# top.net
KiCad netlist of a schematic drawn in Altium Designer
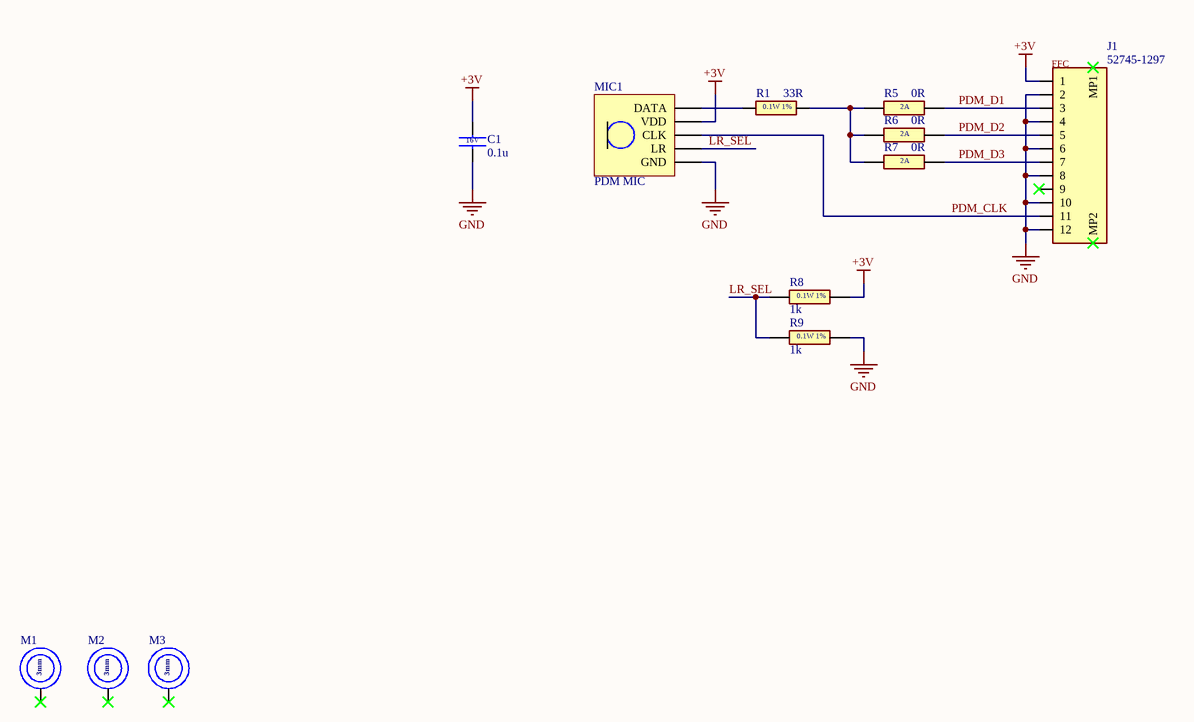
[diagram p0: top.SchDoc]

(export (version "E")
  (design (tool "Eeschema 10.0.6"))
  (components
    (comp (ref "C1")
      (value "0.1u")
      (footprint "CAPC1608X95N")
      (description "16V 0.1uF XR7 0603 10%")
      (fields
        (field (name "MANUFACTURER_PART_NUMBER") "C0603C104K4RAC-TU")
        (field (name "MOUSER PART NUMBER") "80-C0603C104K4RAC")
      )
      (libsource (lib "bch-lib") (part "ECK+100n16V"))
    )
    (comp (ref "J1")
      (value "52745-1297")
      (footprint "527451297")
      (fields (field (name "MOUSER PART NUMBER") "538-52745-1297"))
      (libsource (lib "bch-lib") (part "EJ+52745-1297"))
    )
    (comp (ref "M1")
      (value "MTH-3MM")
      (footprint "MountingHole_3.0mm_NPTH")
      (libsource (lib "bch-lib") (part "EMECH-MTH-3MM"))
    )
    (comp (ref "M2")
      (value "MTH-3MM")
      (footprint "MountingHole_3.0mm_NPTH")
      (libsource (lib "bch-lib") (part "EMECH-MTH-3MM"))
    )
    (comp (ref "M3")
      (value "MTH-3MM")
      (footprint "MountingHole_3.0mm_NPTH")
      (libsource (lib "bch-lib") (part "EMECH-MTH-3MM"))
    )
    (comp (ref "MIC1")
      (value "PDM MIC")
      (footprint "LLGA-5-4X3")
      (description "MEMS Microphones MIC DBP DIGITAL")
      (libsource (lib "bch-lib") (part "EX+IM67D130AXTSA2"))
    )
    (comp (ref "R1")
      (value "33R")
      (footprint "RESC1608X55N")
      (description "Resistor 1% 0.1W")
      (fields
        (field (name "MANUFACTURER_PART_NUMBER") "0603WAF330JT5E")
        (field (name "MOUSER PART NUMBER") "303-0603WAF330JT5E")
      )
      (libsource (lib "bch-lib") (part "ER+33R"))
    )
    (comp (ref "R5")
      (value "0R")
      (footprint "RESC1608X50N")
      (description "2A")
      (fields
        (field (name "MANUFACTURER_PART_NUMBER") "RCA06030000ZSEA")
        (field (name "MOUSER PART NUMBER") "71-RCA06030000ZSEA")
      )
      (libsource (lib "bch-lib") (part "ER+0R"))
    )
    (comp (ref "R6")
      (value "0R")
      (footprint "RESC1608X50N")
      (description "2A")
      (fields
        (field (name "MANUFACTURER_PART_NUMBER") "RCA06030000ZSEA")
        (field (name "MOUSER PART NUMBER") "71-RCA06030000ZSEA")
      )
      (libsource (lib "bch-lib") (part "ER+0R"))
    )
    (comp (ref "R7")
      (value "0R")
      (footprint "RESC1608X50N")
      (description "2A")
      (fields
        (field (name "MANUFACTURER_PART_NUMBER") "RCA06030000ZSEA")
        (field (name "MOUSER PART NUMBER") "71-RCA06030000ZSEA")
      )
      (libsource (lib "bch-lib") (part "ER+0R"))
    )
    (comp (ref "R8")
      (value "1k")
      (footprint "RESC1608X50N")
      (description "Resistor 1%, 0.1W")
      (fields
        (field (name "MANUFACTURER_PART_NUMBER") "CRCW06031K00FKEA")
        (field (name "MOUSER PART NUMBER") "71-CRCW0603-1.0K-E3")
      )
      (libsource (lib "bch-lib") (part "ER+1K"))
    )
    (comp (ref "R9")
      (value "1k")
      (footprint "RESC1608X50N")
      (description "Resistor 1%, 0.1W")
      (fields
        (field (name "MANUFACTURER_PART_NUMBER") "CRCW06031K00FKEA")
        (field (name "MOUSER PART NUMBER") "71-CRCW0603-1.0K-E3")
      )
      (libsource (lib "bch-lib") (part "ER+1K"))
    )
  )
  (nets
    (net (code "1") (name "+3V") (class "Default")
      (node (ref "C1") (pin "1") (pinfunction "1_1") (pintype "passive"))
      (node (ref "J1") (pin "1") (pinfunction "1_1") (pintype "passive"))
      (node (ref "MIC1") (pin "4") (pinfunction "VDD_4") (pintype "passive"))
      (node (ref "R8") (pin "2") (pinfunction "2_2") (pintype "passive"))
    )
    (net (code "2") (name "/LR_SEL") (class "Default")
      (node (ref "MIC1") (pin "2") (pinfunction "LR_2") (pintype "passive"))
      (node (ref "R8") (pin "1") (pinfunction "1_1") (pintype "passive"))
      (node (ref "R9") (pin "1") (pinfunction "1_1") (pintype "passive"))
    )
    (net (code "3") (name "/PDM_CLK") (class "Default")
      (node (ref "J1") (pin "11") (pinfunction "11_11") (pintype "passive"))
      (node (ref "MIC1") (pin "1") (pinfunction "CLK_1") (pintype "passive"))
    )
    (net (code "4") (name "/PDM_D1") (class "Default")
      (node (ref "J1") (pin "3") (pinfunction "3_3") (pintype "passive"))
      (node (ref "R5") (pin "2") (pinfunction "2_2") (pintype "passive"))
    )
    (net (code "5") (name "/PDM_D2") (class "Default")
      (node (ref "J1") (pin "5") (pinfunction "5_5") (pintype "passive"))
      (node (ref "R6") (pin "2") (pinfunction "2_2") (pintype "passive"))
    )
    (net (code "6") (name "/PDM_D3") (class "Default")
      (node (ref "J1") (pin "7") (pinfunction "7_7") (pintype "passive"))
      (node (ref "R7") (pin "2") (pinfunction "2_2") (pintype "passive"))
    )
    (net (code "7") (name "GND") (class "Default")
      (node (ref "C1") (pin "2") (pinfunction "2_2") (pintype "passive"))
      (node (ref "J1") (pin "10") (pinfunction "10_10") (pintype "passive"))
      (node (ref "J1") (pin "12") (pinfunction "12_12") (pintype "passive"))
      (node (ref "J1") (pin "2") (pinfunction "2_2") (pintype "passive"))
      (node (ref "J1") (pin "4") (pinfunction "4_4") (pintype "passive"))
      (node (ref "J1") (pin "6") (pinfunction "6_6") (pintype "passive"))
      (node (ref "J1") (pin "8") (pinfunction "8_8") (pintype "passive"))
      (node (ref "MIC1") (pin "5") (pinfunction "GND_5") (pintype "passive"))
      (node (ref "R9") (pin "2") (pinfunction "2_2") (pintype "passive"))
    )
    (net (code "8") (name "Net-(MIC1-DATA)") (class "Default")
      (node (ref "MIC1") (pin "3") (pinfunction "DATA_3") (pintype "passive"))
      (node (ref "R1") (pin "1") (pinfunction "1_1") (pintype "passive"))
    )
    (net (code "9") (name "Net-(R1-Pad2)") (class "Default")
      (node (ref "R1") (pin "2") (pinfunction "2_2") (pintype "passive"))
      (node (ref "R5") (pin "1") (pinfunction "1_1") (pintype "passive"))
      (node (ref "R6") (pin "1") (pinfunction "1_1") (pintype "passive"))
      (node (ref "R7") (pin "1") (pinfunction "1_1") (pintype "passive"))
    )
    (net (code "10") (name "unconnected-(J1-Pad9)") (class "Default")
      (node (ref "J1") (pin "9") (pinfunction "9_9") (pintype "passive+no_connect"))
    )
    (net (code "11") (name "unconnected-(J1-PadMP1)") (class "Default")
      (node (ref "J1") (pin "MP1") (pinfunction "MP1_MP1") (pintype "passive+no_connect"))
    )
    (net (code "12") (name "unconnected-(J1-PadMP2)") (class "Default")
      (node (ref "J1") (pin "MP2") (pinfunction "MP2_MP2") (pintype "passive+no_connect"))
    )
    (net (code "13") (name "unconnected-(M1-Pad1)") (class "Default")
      (node (ref "M1") (pin "1") (pinfunction "1_1") (pintype "passive+no_connect"))
    )
    (net (code "14") (name "unconnected-(M2-Pad1)") (class "Default")
      (node (ref "M2") (pin "1") (pinfunction "1_1") (pintype "passive+no_connect"))
    )
    (net (code "15") (name "unconnected-(M3-Pad1)") (class "Default")
      (node (ref "M3") (pin "1") (pinfunction "1_1") (pintype "passive+no_connect"))
    )
  )
)
